# pan3029m.net
KiCad netlist of a schematic drawn in Altium Designer
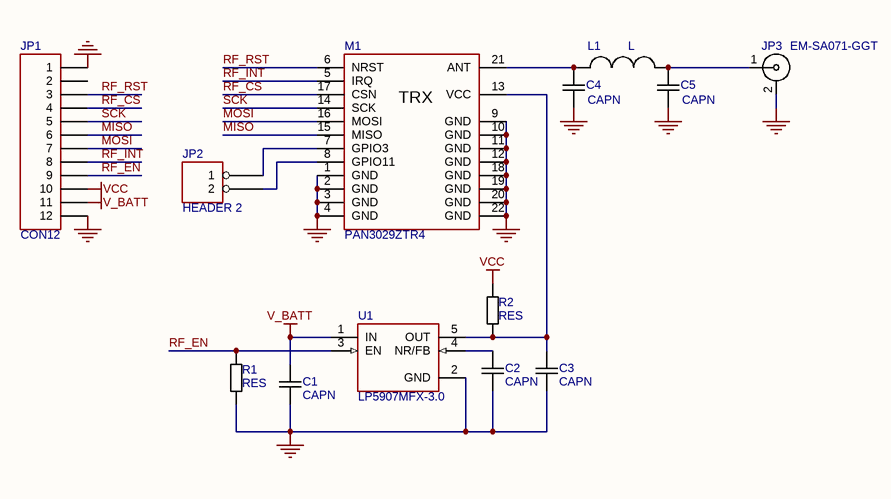
[diagram p0: pan3029m.SchDoc]

(export (version "E")
  (design (tool "Eeschema 10.0.6"))
  (components
    (comp (ref "C1")
      (value "CAPN")
      (footprint "C-0805")
      (fields (field (name "VOLTAGE") "50V"))
      (libsource (lib "Passive") (part "CAPN"))
    )
    (comp (ref "C2")
      (value "CAPN")
      (footprint "C-0603")
      (fields (field (name "VOLTAGE") "50V"))
      (libsource (lib "Passive") (part "CAPN"))
    )
    (comp (ref "C3")
      (value "CAPN")
      (footprint "C-0805")
      (fields (field (name "VOLTAGE") "50V"))
      (libsource (lib "Passive") (part "CAPN"))
    )
    (comp (ref "C4")
      (value "CAPN")
      (footprint "C-0603")
      (fields (field (name "VOLTAGE") "50V"))
      (libsource (lib "Passive") (part "CAPN"))
    )
    (comp (ref "C5")
      (value "CAPN")
      (footprint "C-0603")
      (fields (field (name "VOLTAGE") "50V"))
      (libsource (lib "Passive") (part "CAPN"))
    )
    (comp (ref "JP1")
      (value "CON12")
      (footprint "PBS1-12R")
      (description "Connector")
      (libsource (lib "Connectors") (part "CON12"))
    )
    (comp (ref "JP2")
      (value "HEADER 2")
      (footprint "PLS1-2")
      (libsource (lib "Connectors") (part "HEADER 2"))
    )
    (comp (ref "JP3")
      (value "EM-SA071-GGT")
      (footprint "SMA_F_EDGE")
      (description "SMA Female R/A PCB Mount")
      (libsource (lib "Connectors") (part "SMA"))
    )
    (comp (ref "L1") (value "L") (footprint "L-0603") (libsource (lib "Passive") (part "L")))
    (comp (ref "M1")
      (value "PAN3029ZTR4")
      (footprint "PAN3029ZTR")
      (libsource (lib "RFmodules") (part "PAN3029ZTR"))
    )
    (comp (ref "R1") (value "RES") (footprint "R-0603") (libsource (lib "Passive") (part "RES")))
    (comp (ref "R2") (value "RES") (footprint "R-0603") (libsource (lib "Passive") (part "RES")))
    (comp (ref "U1")
      (value "LP5907MFX-3.0")
      (footprint "SOT-23-5")
      (description "250mA Low-Dropout Regulator")
      (libsource (lib "ICs") (part "LP5907"))
    )
  )
  (nets
    (net (code "1") (name "/MISO") (class "Default")
      (node (ref "JP1") (pin "6") (pinfunction "6_6") (pintype "passive"))
      (node (ref "M1") (pin "15") (pinfunction "MISO_15") (pintype "passive"))
    )
    (net (code "2") (name "/MOSI") (class "Default")
      (node (ref "JP1") (pin "7") (pinfunction "7_7") (pintype "passive"))
      (node (ref "M1") (pin "16") (pinfunction "MOSI_16") (pintype "passive"))
    )
    (net (code "3") (name "/RF_CS") (class "Default")
      (node (ref "JP1") (pin "4") (pinfunction "4_4") (pintype "passive"))
      (node (ref "M1") (pin "17") (pinfunction "CSN_17") (pintype "passive"))
    )
    (net (code "4") (name "/RF_EN") (class "Default")
      (node (ref "JP1") (pin "9") (pinfunction "9_9") (pintype "passive"))
      (node (ref "R1") (pin "2") (pinfunction "2_2") (pintype "passive"))
      (node (ref "U1") (pin "3") (pinfunction "EN_3") (pintype "input"))
    )
    (net (code "5") (name "/RF_INT") (class "Default")
      (node (ref "JP1") (pin "8") (pinfunction "8_8") (pintype "passive"))
      (node (ref "M1") (pin "5") (pinfunction "IRQ_5") (pintype "passive"))
    )
    (net (code "6") (name "/RF_RST") (class "Default")
      (node (ref "JP1") (pin "3") (pinfunction "3_3") (pintype "passive"))
      (node (ref "M1") (pin "6") (pinfunction "NRST_6") (pintype "passive"))
    )
    (net (code "7") (name "/SCK") (class "Default")
      (node (ref "JP1") (pin "5") (pinfunction "5_5") (pintype "passive"))
      (node (ref "M1") (pin "14") (pinfunction "SCK_14") (pintype "passive"))
    )
    (net (code "8") (name "GND") (class "Default")
      (node (ref "C1") (pin "2") (pinfunction "2_2") (pintype "passive"))
      (node (ref "C2") (pin "2") (pinfunction "2_2") (pintype "passive"))
      (node (ref "C3") (pin "2") (pinfunction "2_2") (pintype "passive"))
      (node (ref "C4") (pin "2") (pinfunction "2_2") (pintype "passive"))
      (node (ref "C5") (pin "2") (pinfunction "2_2") (pintype "passive"))
      (node (ref "JP1") (pin "1") (pinfunction "1_1") (pintype "passive"))
      (node (ref "JP1") (pin "12") (pinfunction "12_12") (pintype "passive"))
      (node (ref "JP3") (pin "2") (pinfunction "2_2") (pintype "passive"))
      (node (ref "M1") (pin "1") (pinfunction "GND_1") (pintype "passive"))
      (node (ref "M1") (pin "10") (pinfunction "GND_10") (pintype "passive"))
      (node (ref "M1") (pin "11") (pinfunction "GND_11") (pintype "passive"))
      (node (ref "M1") (pin "12") (pinfunction "GND_12") (pintype "passive"))
      (node (ref "M1") (pin "18") (pinfunction "GND_18") (pintype "passive"))
      (node (ref "M1") (pin "19") (pinfunction "GND_19") (pintype "passive"))
      (node (ref "M1") (pin "2") (pinfunction "GND_2") (pintype "passive"))
      (node (ref "M1") (pin "20") (pinfunction "GND_20") (pintype "passive"))
      (node (ref "M1") (pin "22") (pinfunction "GND_22") (pintype "passive"))
      (node (ref "M1") (pin "3") (pinfunction "GND_3") (pintype "passive"))
      (node (ref "M1") (pin "4") (pinfunction "GND_4") (pintype "passive"))
      (node (ref "M1") (pin "9") (pinfunction "GND_9") (pintype "passive"))
      (node (ref "R1") (pin "1") (pinfunction "1_1") (pintype "passive"))
      (node (ref "U1") (pin "2") (pinfunction "GND_2") (pintype "power_in"))
    )
    (net (code "9") (name "Net-(C5-Pad1)") (class "Default")
      (node (ref "C5") (pin "1") (pinfunction "1_1") (pintype "passive"))
      (node (ref "JP3") (pin "1") (pinfunction "1_1") (pintype "passive"))
      (node (ref "L1") (pin "2") (pinfunction "2_2") (pintype "passive"))
    )
    (net (code "10") (name "Net-(M1-ANT)") (class "Default")
      (node (ref "C4") (pin "1") (pinfunction "1_1") (pintype "passive"))
      (node (ref "L1") (pin "1") (pinfunction "1_1") (pintype "passive"))
      (node (ref "M1") (pin "21") (pinfunction "ANT_21") (pintype "passive"))
    )
    (net (code "11") (name "Net-(M1-GPIO3)") (class "Default")
      (node (ref "JP2") (pin "1") (pinfunction "1_1") (pintype "passive"))
      (node (ref "M1") (pin "7") (pinfunction "GPIO3_7") (pintype "passive"))
    )
    (net (code "12") (name "Net-(M1-GPIO11)") (class "Default")
      (node (ref "JP2") (pin "2") (pinfunction "2_2") (pintype "passive"))
      (node (ref "M1") (pin "8") (pinfunction "GPIO11_8") (pintype "passive"))
    )
    (net (code "13") (name "Net-(M1-VCC)") (class "Default")
      (node (ref "C3") (pin "1") (pinfunction "1_1") (pintype "passive"))
      (node (ref "M1") (pin "13") (pinfunction "VCC_13") (pintype "passive"))
      (node (ref "R2") (pin "1") (pinfunction "1_1") (pintype "passive"))
      (node (ref "U1") (pin "5") (pinfunction "OUT_5") (pintype "power_in"))
    )
    (net (code "14") (name "Net-(U1-NR{slash}FB)") (class "Default")
      (node (ref "C2") (pin "1") (pinfunction "1_1") (pintype "passive"))
      (node (ref "U1") (pin "4") (pinfunction "NR/FB_4") (pintype "input"))
    )
    (net (code "15") (name "VCC") (class "Default")
      (node (ref "JP1") (pin "10") (pinfunction "10_10") (pintype "passive"))
      (node (ref "R2") (pin "2") (pinfunction "2_2") (pintype "passive"))
    )
    (net (code "16") (name "V_BATT") (class "Default")
      (node (ref "C1") (pin "1") (pinfunction "1_1") (pintype "passive"))
      (node (ref "JP1") (pin "11") (pinfunction "11_11") (pintype "passive"))
      (node (ref "U1") (pin "1") (pinfunction "IN_1") (pintype "power_in"))
    )
    (net (code "17") (name "unconnected-(JP1-Pad2)") (class "Default")
      (node (ref "JP1") (pin "2") (pinfunction "2_2") (pintype "passive"))
    )
  )
)
